# Touch_Pad_Board_PCB_A.net
KiCad netlist of a schematic drawn in EAGLE
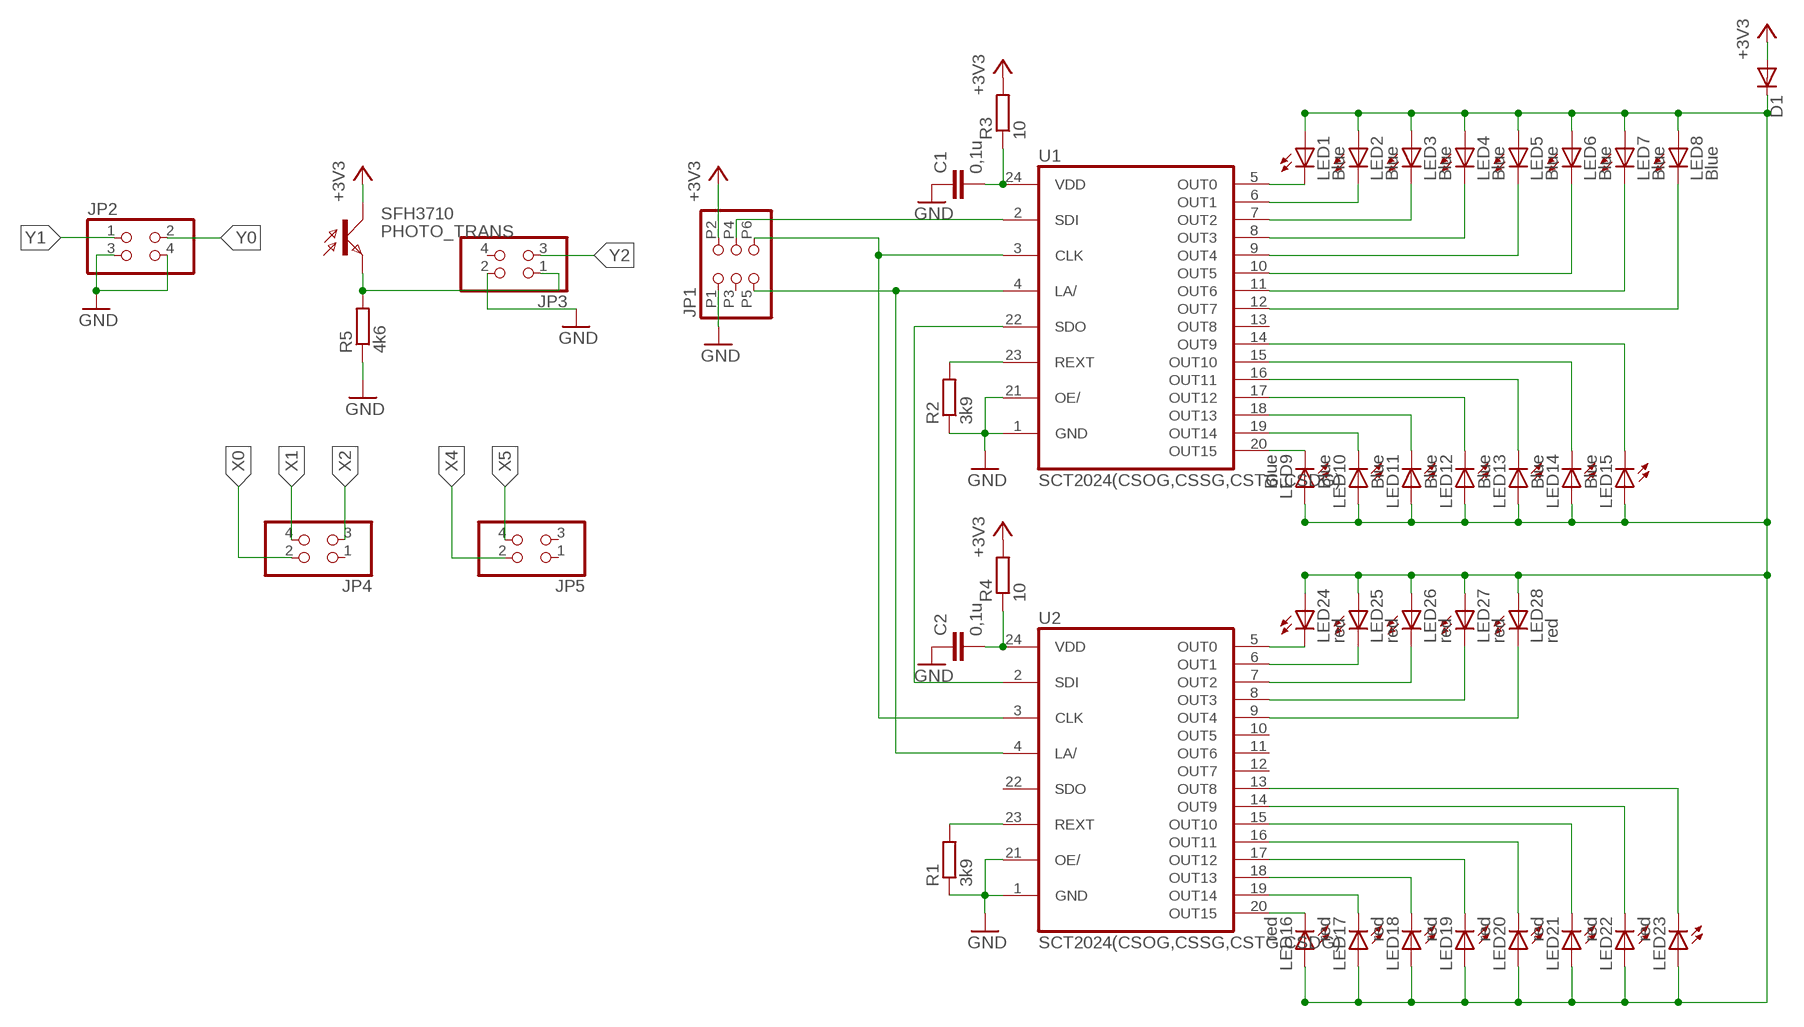
[diagram p0: schematic, sheet 1]

(export (version "E")
  (design (tool "Eeschema 10.0.6"))
  (components
    (comp (ref "C1")
      (value "0,1u")
      (footprint "eagle-import:C0805")
      (libsource (lib "eagle-import") (part "C-EUC0805"))
    )
    (comp (ref "C2")
      (value "0,1u")
      (footprint "eagle-import:C0805")
      (libsource (lib "eagle-import") (part "C-EUC0805"))
    )
    (comp (ref "D1")
      (value "DIODE-DO214AC")
      (footprint "eagle-import:DO214AC")
      (libsource (lib "eagle-import") (part "DIODE-DO214AC"))
    )
    (comp (ref "JP1")
      (value "PINHD-2X3SMD")
      (footprint "eagle-import:2X3SMD")
      (libsource (lib "eagle-import") (part "PINHD-2X3SMD"))
    )
    (comp (ref "JP2")
      (value "PINHD-2X2SMD")
      (footprint "eagle-import:2X2SMD")
      (libsource (lib "eagle-import") (part "PINHD-2X2SMD"))
    )
    (comp (ref "JP3")
      (value "PINHD-2X2SMD")
      (footprint "eagle-import:2X2SMD")
      (libsource (lib "eagle-import") (part "PINHD-2X2SMD"))
    )
    (comp (ref "JP4")
      (value "PINHD-2X2SMD")
      (footprint "eagle-import:2X2SMD")
      (libsource (lib "eagle-import") (part "PINHD-2X2SMD"))
    )
    (comp (ref "JP5")
      (value "PINHD-2X2SMD")
      (footprint "eagle-import:2X2SMD")
      (libsource (lib "eagle-import") (part "PINHD-2X2SMD"))
    )
    (comp (ref "LED1")
      (value "Blue")
      (footprint "eagle-import:CHIPLED_1206")
      (libsource (lib "eagle-import") (part "LEDCHIPLED_1206"))
    )
    (comp (ref "LED2")
      (value "Blue")
      (footprint "eagle-import:CHIPLED_1206")
      (libsource (lib "eagle-import") (part "LEDCHIPLED_1206"))
    )
    (comp (ref "LED3")
      (value "Blue")
      (footprint "eagle-import:CHIPLED_1206")
      (libsource (lib "eagle-import") (part "LEDCHIPLED_1206"))
    )
    (comp (ref "LED4")
      (value "Blue")
      (footprint "eagle-import:CHIPLED_1206")
      (libsource (lib "eagle-import") (part "LEDCHIPLED_1206"))
    )
    (comp (ref "LED5")
      (value "Blue")
      (footprint "eagle-import:CHIPLED_1206")
      (libsource (lib "eagle-import") (part "LEDCHIPLED_1206"))
    )
    (comp (ref "LED6")
      (value "Blue")
      (footprint "eagle-import:CHIPLED_1206")
      (libsource (lib "eagle-import") (part "LEDCHIPLED_1206"))
    )
    (comp (ref "LED7")
      (value "Blue")
      (footprint "eagle-import:CHIPLED_1206")
      (libsource (lib "eagle-import") (part "LEDCHIPLED_1206"))
    )
    (comp (ref "LED8")
      (value "Blue")
      (footprint "eagle-import:CHIPLED_1206")
      (libsource (lib "eagle-import") (part "LEDCHIPLED_1206"))
    )
    (comp (ref "LED9")
      (value "Blue")
      (footprint "eagle-import:CHIPLED_1206")
      (libsource (lib "eagle-import") (part "LEDCHIPLED_1206"))
    )
    (comp (ref "LED10")
      (value "Blue")
      (footprint "eagle-import:CHIPLED_1206")
      (libsource (lib "eagle-import") (part "LEDCHIPLED_1206"))
    )
    (comp (ref "LED11")
      (value "Blue")
      (footprint "eagle-import:CHIPLED_1206")
      (libsource (lib "eagle-import") (part "LEDCHIPLED_1206"))
    )
    (comp (ref "LED12")
      (value "Blue")
      (footprint "eagle-import:CHIPLED_1206")
      (libsource (lib "eagle-import") (part "LEDCHIPLED_1206"))
    )
    (comp (ref "LED13")
      (value "Blue")
      (footprint "eagle-import:CHIPLED_1206")
      (libsource (lib "eagle-import") (part "LEDCHIPLED_1206"))
    )
    (comp (ref "LED14")
      (value "Blue")
      (footprint "eagle-import:CHIPLED_1206")
      (libsource (lib "eagle-import") (part "LEDCHIPLED_1206"))
    )
    (comp (ref "LED15")
      (value "Blue")
      (footprint "eagle-import:CHIPLED_1206")
      (libsource (lib "eagle-import") (part "LEDCHIPLED_1206"))
    )
    (comp (ref "LED16")
      (value "red")
      (footprint "eagle-import:CHIPLED_1206")
      (libsource (lib "eagle-import") (part "LEDCHIPLED_1206"))
    )
    (comp (ref "LED17")
      (value "red")
      (footprint "eagle-import:CHIPLED_1206")
      (libsource (lib "eagle-import") (part "LEDCHIPLED_1206"))
    )
    (comp (ref "LED18")
      (value "red")
      (footprint "eagle-import:CHIPLED_1206")
      (libsource (lib "eagle-import") (part "LEDCHIPLED_1206"))
    )
    (comp (ref "LED19")
      (value "red")
      (footprint "eagle-import:CHIPLED_1206")
      (libsource (lib "eagle-import") (part "LEDCHIPLED_1206"))
    )
    (comp (ref "LED20")
      (value "red")
      (footprint "eagle-import:CHIPLED_1206")
      (libsource (lib "eagle-import") (part "LEDCHIPLED_1206"))
    )
    (comp (ref "LED21")
      (value "red")
      (footprint "eagle-import:CHIPLED_1206")
      (libsource (lib "eagle-import") (part "LEDCHIPLED_1206"))
    )
    (comp (ref "LED22")
      (value "red")
      (footprint "eagle-import:CHIPLED_1206")
      (libsource (lib "eagle-import") (part "LEDCHIPLED_1206"))
    )
    (comp (ref "LED23")
      (value "red")
      (footprint "eagle-import:CHIPLED_1206")
      (libsource (lib "eagle-import") (part "LEDCHIPLED_1206"))
    )
    (comp (ref "LED24")
      (value "red")
      (footprint "eagle-import:CHIPLED_1206")
      (libsource (lib "eagle-import") (part "LEDCHIPLED_1206"))
    )
    (comp (ref "LED25")
      (value "red")
      (footprint "eagle-import:CHIPLED_1206")
      (libsource (lib "eagle-import") (part "LEDCHIPLED_1206"))
    )
    (comp (ref "LED26")
      (value "red")
      (footprint "eagle-import:CHIPLED_1206")
      (libsource (lib "eagle-import") (part "LEDCHIPLED_1206"))
    )
    (comp (ref "LED27")
      (value "red")
      (footprint "eagle-import:CHIPLED_1206")
      (libsource (lib "eagle-import") (part "LEDCHIPLED_1206"))
    )
    (comp (ref "LED28")
      (value "red")
      (footprint "eagle-import:CHIPLED_1206")
      (libsource (lib "eagle-import") (part "LEDCHIPLED_1206"))
    )
    (comp (ref "R1")
      (value "3k9")
      (footprint "eagle-import:R0805")
      (libsource (lib "eagle-import") (part "R-EU_R0805"))
    )
    (comp (ref "R2")
      (value "3k9")
      (footprint "eagle-import:R0805")
      (libsource (lib "eagle-import") (part "R-EU_R0805"))
    )
    (comp (ref "R3")
      (value "10")
      (footprint "eagle-import:R0805")
      (libsource (lib "eagle-import") (part "R-EU_R0805"))
    )
    (comp (ref "R4")
      (value "10")
      (footprint "eagle-import:R0805")
      (libsource (lib "eagle-import") (part "R-EU_R0805"))
    )
    (comp (ref "R5")
      (value "4k6")
      (footprint "eagle-import:R0805")
      (libsource (lib "eagle-import") (part "R-EU_R0805"))
    )
    (comp (ref "SFH3710")
      (value "PHOTO_TRANS")
      (footprint "eagle-import:PHOTO_TRANS")
      (libsource (lib "eagle-import") (part "PHOTO_TRANS"))
    )
    (comp (ref "U1")
      (value "SCT2024(CSOG,CSSG,CSTG,CSDG)")
      (footprint "eagle-import:24SSOP")
      (libsource (lib "eagle-import") (part "SCT2024(CSOG,CSSG,CSTG,CSDG)"))
    )
    (comp (ref "U2")
      (value "SCT2024(CSOG,CSSG,CSTG,CSDG)")
      (footprint "eagle-import:24SSOP")
      (libsource (lib "eagle-import") (part "SCT2024(CSOG,CSSG,CSTG,CSDG)"))
    )
  )
  (nets
    (net (code "1") (name "+3V3") (class "Default")
      (node (ref "D1") (pin "A") (pinfunction "A_A") (pintype "passive"))
      (node (ref "JP1") (pin "P2") (pinfunction "2_P2") (pintype "passive"))
      (node (ref "R3") (pin "2") (pinfunction "2_2") (pintype "passive"))
      (node (ref "R4") (pin "2") (pinfunction "2_2") (pintype "passive"))
      (node (ref "SFH3710") (pin "A") (pinfunction "C_A") (pintype "passive"))
    )
    (net (code "2") (name "GND") (class "Default")
      (node (ref "C1") (pin "1") (pinfunction "1_1") (pintype "passive"))
      (node (ref "C2") (pin "1") (pinfunction "1_1") (pintype "passive"))
      (node (ref "JP1") (pin "P1") (pinfunction "1_P1") (pintype "passive"))
      (node (ref "JP2") (pin "3") (pinfunction "3_3") (pintype "passive"))
      (node (ref "JP2") (pin "4") (pinfunction "4_4") (pintype "passive"))
      (node (ref "JP3") (pin "2") (pinfunction "2_2") (pintype "passive"))
      (node (ref "R1") (pin "1") (pinfunction "1_1") (pintype "passive"))
      (node (ref "R2") (pin "1") (pinfunction "1_1") (pintype "passive"))
      (node (ref "R5") (pin "1") (pinfunction "1_1") (pintype "passive"))
      (node (ref "U1") (pin "1") (pinfunction "GND_1") (pintype "power_in"))
      (node (ref "U1") (pin "21") (pinfunction "OE/_21") (pintype "bidirectional"))
      (node (ref "U2") (pin "1") (pinfunction "GND_1") (pintype "power_in"))
      (node (ref "U2") (pin "21") (pinfunction "OE/_21") (pintype "bidirectional"))
    )
    (net (code "3") (name "Net-(D1-PadC)") (class "Default")
      (node (ref "D1") (pin "C") (pinfunction "C_C") (pintype "passive"))
      (node (ref "LED1") (pin "A") (pinfunction "A_A") (pintype "passive"))
      (node (ref "LED10") (pin "A") (pinfunction "A_A") (pintype "passive"))
      (node (ref "LED11") (pin "A") (pinfunction "A_A") (pintype "passive"))
      (node (ref "LED12") (pin "A") (pinfunction "A_A") (pintype "passive"))
      (node (ref "LED13") (pin "A") (pinfunction "A_A") (pintype "passive"))
      (node (ref "LED14") (pin "A") (pinfunction "A_A") (pintype "passive"))
      (node (ref "LED15") (pin "A") (pinfunction "A_A") (pintype "passive"))
      (node (ref "LED16") (pin "A") (pinfunction "A_A") (pintype "passive"))
      (node (ref "LED17") (pin "A") (pinfunction "A_A") (pintype "passive"))
      (node (ref "LED18") (pin "A") (pinfunction "A_A") (pintype "passive"))
      (node (ref "LED19") (pin "A") (pinfunction "A_A") (pintype "passive"))
      (node (ref "LED2") (pin "A") (pinfunction "A_A") (pintype "passive"))
      (node (ref "LED20") (pin "A") (pinfunction "A_A") (pintype "passive"))
      (node (ref "LED21") (pin "A") (pinfunction "A_A") (pintype "passive"))
      (node (ref "LED22") (pin "A") (pinfunction "A_A") (pintype "passive"))
      (node (ref "LED23") (pin "A") (pinfunction "A_A") (pintype "passive"))
      (node (ref "LED24") (pin "A") (pinfunction "A_A") (pintype "passive"))
      (node (ref "LED25") (pin "A") (pinfunction "A_A") (pintype "passive"))
      (node (ref "LED26") (pin "A") (pinfunction "A_A") (pintype "passive"))
      (node (ref "LED27") (pin "A") (pinfunction "A_A") (pintype "passive"))
      (node (ref "LED28") (pin "A") (pinfunction "A_A") (pintype "passive"))
      (node (ref "LED3") (pin "A") (pinfunction "A_A") (pintype "passive"))
      (node (ref "LED4") (pin "A") (pinfunction "A_A") (pintype "passive"))
      (node (ref "LED5") (pin "A") (pinfunction "A_A") (pintype "passive"))
      (node (ref "LED6") (pin "A") (pinfunction "A_A") (pintype "passive"))
      (node (ref "LED7") (pin "A") (pinfunction "A_A") (pintype "passive"))
      (node (ref "LED8") (pin "A") (pinfunction "A_A") (pintype "passive"))
      (node (ref "LED9") (pin "A") (pinfunction "A_A") (pintype "passive"))
    )
    (net (code "4") (name "Net-(JP1-4)") (class "Default")
      (node (ref "JP1") (pin "P4") (pinfunction "4_P4") (pintype "passive"))
      (node (ref "U1") (pin "2") (pinfunction "SDI_2") (pintype "input"))
    )
    (net (code "5") (name "Net-(JP1-5)") (class "Default")
      (node (ref "JP1") (pin "P5") (pinfunction "5_P5") (pintype "passive"))
      (node (ref "U1") (pin "4") (pinfunction "LA/_4") (pintype "bidirectional"))
      (node (ref "U2") (pin "4") (pinfunction "LA/_4") (pintype "bidirectional"))
    )
    (net (code "6") (name "Net-(JP1-6)") (class "Default")
      (node (ref "JP1") (pin "P6") (pinfunction "6_P6") (pintype "passive"))
      (node (ref "U1") (pin "3") (pinfunction "CLK_3") (pintype "input"))
      (node (ref "U2") (pin "3") (pinfunction "CLK_3") (pintype "input"))
    )
    (net (code "7") (name "Net-(SFH3710-E)") (class "Default")
      (node (ref "JP3") (pin "1") (pinfunction "1_1") (pintype "passive"))
      (node (ref "R5") (pin "2") (pinfunction "2_2") (pintype "passive"))
      (node (ref "SFH3710") (pin "C") (pinfunction "E_C") (pintype "passive"))
    )
    (net (code "8") (name "Net-(U1-OUT0)") (class "Default")
      (node (ref "LED1") (pin "C") (pinfunction "C_C") (pintype "passive"))
      (node (ref "U1") (pin "5") (pinfunction "OUT0_5") (pintype "output"))
    )
    (net (code "9") (name "Net-(U1-OUT1)") (class "Default")
      (node (ref "LED2") (pin "C") (pinfunction "C_C") (pintype "passive"))
      (node (ref "U1") (pin "6") (pinfunction "OUT1_6") (pintype "output"))
    )
    (net (code "10") (name "Net-(U1-OUT2)") (class "Default")
      (node (ref "LED3") (pin "C") (pinfunction "C_C") (pintype "passive"))
      (node (ref "U1") (pin "7") (pinfunction "OUT2_7") (pintype "output"))
    )
    (net (code "11") (name "Net-(U1-OUT3)") (class "Default")
      (node (ref "LED4") (pin "C") (pinfunction "C_C") (pintype "passive"))
      (node (ref "U1") (pin "8") (pinfunction "OUT3_8") (pintype "output"))
    )
    (net (code "12") (name "Net-(U1-OUT4)") (class "Default")
      (node (ref "LED5") (pin "C") (pinfunction "C_C") (pintype "passive"))
      (node (ref "U1") (pin "9") (pinfunction "OUT4_9") (pintype "output"))
    )
    (net (code "13") (name "Net-(U1-OUT5)") (class "Default")
      (node (ref "LED6") (pin "C") (pinfunction "C_C") (pintype "passive"))
      (node (ref "U1") (pin "10") (pinfunction "OUT5_10") (pintype "output"))
    )
    (net (code "14") (name "Net-(U1-OUT6)") (class "Default")
      (node (ref "LED7") (pin "C") (pinfunction "C_C") (pintype "passive"))
      (node (ref "U1") (pin "11") (pinfunction "OUT6_11") (pintype "output"))
    )
    (net (code "15") (name "Net-(U1-OUT7)") (class "Default")
      (node (ref "LED8") (pin "C") (pinfunction "C_C") (pintype "passive"))
      (node (ref "U1") (pin "12") (pinfunction "OUT7_12") (pintype "output"))
    )
    (net (code "16") (name "Net-(U1-OUT9)") (class "Default")
      (node (ref "LED15") (pin "C") (pinfunction "C_C") (pintype "passive"))
      (node (ref "U1") (pin "14") (pinfunction "OUT9_14") (pintype "output"))
    )
    (net (code "17") (name "Net-(U1-OUT10)") (class "Default")
      (node (ref "LED14") (pin "C") (pinfunction "C_C") (pintype "passive"))
      (node (ref "U1") (pin "15") (pinfunction "OUT10_15") (pintype "output"))
    )
    (net (code "18") (name "Net-(U1-OUT11)") (class "Default")
      (node (ref "LED13") (pin "C") (pinfunction "C_C") (pintype "passive"))
      (node (ref "U1") (pin "16") (pinfunction "OUT11_16") (pintype "output"))
    )
    (net (code "19") (name "Net-(U1-OUT12)") (class "Default")
      (node (ref "LED12") (pin "C") (pinfunction "C_C") (pintype "passive"))
      (node (ref "U1") (pin "17") (pinfunction "OUT12_17") (pintype "output"))
    )
    (net (code "20") (name "Net-(U1-OUT13)") (class "Default")
      (node (ref "LED11") (pin "C") (pinfunction "C_C") (pintype "passive"))
      (node (ref "U1") (pin "18") (pinfunction "OUT13_18") (pintype "output"))
    )
    (net (code "21") (name "Net-(U1-OUT14)") (class "Default")
      (node (ref "LED10") (pin "C") (pinfunction "C_C") (pintype "passive"))
      (node (ref "U1") (pin "19") (pinfunction "OUT14_19") (pintype "output"))
    )
    (net (code "22") (name "Net-(U1-OUT15)") (class "Default")
      (node (ref "LED9") (pin "C") (pinfunction "C_C") (pintype "passive"))
      (node (ref "U1") (pin "20") (pinfunction "OUT15_20") (pintype "output"))
    )
    (net (code "23") (name "Net-(U1-REXT)") (class "Default")
      (node (ref "R2") (pin "2") (pinfunction "2_2") (pintype "passive"))
      (node (ref "U1") (pin "23") (pinfunction "REXT_23") (pintype "power_in"))
    )
    (net (code "24") (name "Net-(U1-SDO)") (class "Default")
      (node (ref "U1") (pin "22") (pinfunction "SDO_22") (pintype "output"))
      (node (ref "U2") (pin "2") (pinfunction "SDI_2") (pintype "input"))
    )
    (net (code "25") (name "Net-(U1-VDD)") (class "Default")
      (node (ref "C1") (pin "2") (pinfunction "2_2") (pintype "passive"))
      (node (ref "R3") (pin "1") (pinfunction "1_1") (pintype "passive"))
      (node (ref "U1") (pin "24") (pinfunction "VDD_24") (pintype "bidirectional"))
    )
    (net (code "26") (name "Net-(U2-OUT0)") (class "Default")
      (node (ref "LED24") (pin "C") (pinfunction "C_C") (pintype "passive"))
      (node (ref "U2") (pin "5") (pinfunction "OUT0_5") (pintype "output"))
    )
    (net (code "27") (name "Net-(U2-OUT1)") (class "Default")
      (node (ref "LED25") (pin "C") (pinfunction "C_C") (pintype "passive"))
      (node (ref "U2") (pin "6") (pinfunction "OUT1_6") (pintype "output"))
    )
    (net (code "28") (name "Net-(U2-OUT2)") (class "Default")
      (node (ref "LED26") (pin "C") (pinfunction "C_C") (pintype "passive"))
      (node (ref "U2") (pin "7") (pinfunction "OUT2_7") (pintype "output"))
    )
    (net (code "29") (name "Net-(U2-OUT3)") (class "Default")
      (node (ref "LED27") (pin "C") (pinfunction "C_C") (pintype "passive"))
      (node (ref "U2") (pin "8") (pinfunction "OUT3_8") (pintype "output"))
    )
    (net (code "30") (name "Net-(U2-OUT4)") (class "Default")
      (node (ref "LED28") (pin "C") (pinfunction "C_C") (pintype "passive"))
      (node (ref "U2") (pin "9") (pinfunction "OUT4_9") (pintype "output"))
    )
    (net (code "31") (name "Net-(U2-OUT8)") (class "Default")
      (node (ref "LED23") (pin "C") (pinfunction "C_C") (pintype "passive"))
      (node (ref "U2") (pin "13") (pinfunction "OUT8_13") (pintype "output"))
    )
    (net (code "32") (name "Net-(U2-OUT9)") (class "Default")
      (node (ref "LED22") (pin "C") (pinfunction "C_C") (pintype "passive"))
      (node (ref "U2") (pin "14") (pinfunction "OUT9_14") (pintype "output"))
    )
    (net (code "33") (name "Net-(U2-OUT10)") (class "Default")
      (node (ref "LED21") (pin "C") (pinfunction "C_C") (pintype "passive"))
      (node (ref "U2") (pin "15") (pinfunction "OUT10_15") (pintype "output"))
    )
    (net (code "34") (name "Net-(U2-OUT11)") (class "Default")
      (node (ref "LED20") (pin "C") (pinfunction "C_C") (pintype "passive"))
      (node (ref "U2") (pin "16") (pinfunction "OUT11_16") (pintype "output"))
    )
    (net (code "35") (name "Net-(U2-OUT12)") (class "Default")
      (node (ref "LED19") (pin "C") (pinfunction "C_C") (pintype "passive"))
      (node (ref "U2") (pin "17") (pinfunction "OUT12_17") (pintype "output"))
    )
    (net (code "36") (name "Net-(U2-OUT13)") (class "Default")
      (node (ref "LED18") (pin "C") (pinfunction "C_C") (pintype "passive"))
      (node (ref "U2") (pin "18") (pinfunction "OUT13_18") (pintype "output"))
    )
    (net (code "37") (name "Net-(U2-OUT14)") (class "Default")
      (node (ref "LED17") (pin "C") (pinfunction "C_C") (pintype "passive"))
      (node (ref "U2") (pin "19") (pinfunction "OUT14_19") (pintype "output"))
    )
    (net (code "38") (name "Net-(U2-OUT15)") (class "Default")
      (node (ref "LED16") (pin "C") (pinfunction "C_C") (pintype "passive"))
      (node (ref "U2") (pin "20") (pinfunction "OUT15_20") (pintype "output"))
    )
    (net (code "39") (name "Net-(U2-REXT)") (class "Default")
      (node (ref "R1") (pin "2") (pinfunction "2_2") (pintype "passive"))
      (node (ref "U2") (pin "23") (pinfunction "REXT_23") (pintype "power_in"))
    )
    (net (code "40") (name "Net-(U2-VDD)") (class "Default")
      (node (ref "C2") (pin "2") (pinfunction "2_2") (pintype "passive"))
      (node (ref "R4") (pin "1") (pinfunction "1_1") (pintype "passive"))
      (node (ref "U2") (pin "24") (pinfunction "VDD_24") (pintype "bidirectional"))
    )
    (net (code "41") (name "X0") (class "Default")
      (node (ref "JP4") (pin "2") (pinfunction "2_2") (pintype "passive"))
    )
    (net (code "42") (name "X1") (class "Default")
      (node (ref "JP4") (pin "4") (pinfunction "4_4") (pintype "passive"))
    )
    (net (code "43") (name "X2") (class "Default")
      (node (ref "JP4") (pin "3") (pinfunction "3_3") (pintype "passive"))
    )
    (net (code "44") (name "X4") (class "Default")
      (node (ref "JP5") (pin "2") (pinfunction "2_2") (pintype "passive"))
    )
    (net (code "45") (name "X5") (class "Default")
      (node (ref "JP5") (pin "4") (pinfunction "4_4") (pintype "passive"))
    )
    (net (code "46") (name "Y0") (class "Default")
      (node (ref "JP2") (pin "2") (pinfunction "2_2") (pintype "passive"))
    )
    (net (code "47") (name "Y1") (class "Default")
      (node (ref "JP2") (pin "1") (pinfunction "1_1") (pintype "passive"))
    )
    (net (code "48") (name "Y2") (class "Default")
      (node (ref "JP3") (pin "3") (pinfunction "3_3") (pintype "passive"))
    )
    (net (code "49") (name "unconnected-(JP1-3-PadP3)") (class "Default")
      (node (ref "JP1") (pin "P3") (pinfunction "3_P3") (pintype "passive"))
    )
    (net (code "50") (name "unconnected-(JP3-Pad4)") (class "Default")
      (node (ref "JP3") (pin "4") (pinfunction "4_4") (pintype "passive"))
    )
    (net (code "51") (name "unconnected-(JP4-Pad1)") (class "Default")
      (node (ref "JP4") (pin "1") (pinfunction "1_1") (pintype "passive"))
    )
    (net (code "52") (name "unconnected-(JP5-Pad1)") (class "Default")
      (node (ref "JP5") (pin "1") (pinfunction "1_1") (pintype "passive"))
    )
    (net (code "53") (name "unconnected-(JP5-Pad3)") (class "Default")
      (node (ref "JP5") (pin "3") (pinfunction "3_3") (pintype "passive"))
    )
    (net (code "54") (name "unconnected-(U1-OUT8-Pad13)") (class "Default")
      (node (ref "U1") (pin "13") (pinfunction "OUT8_13") (pintype "output"))
    )
    (net (code "55") (name "unconnected-(U2-OUT5-Pad10)") (class "Default")
      (node (ref "U2") (pin "10") (pinfunction "OUT5_10") (pintype "output"))
    )
    (net (code "56") (name "unconnected-(U2-OUT6-Pad11)") (class "Default")
      (node (ref "U2") (pin "11") (pinfunction "OUT6_11") (pintype "output"))
    )
    (net (code "57") (name "unconnected-(U2-OUT7-Pad12)") (class "Default")
      (node (ref "U2") (pin "12") (pinfunction "OUT7_12") (pintype "output"))
    )
    (net (code "58") (name "unconnected-(U2-SDO-Pad22)") (class "Default")
      (node (ref "U2") (pin "22") (pinfunction "SDO_22") (pintype "output"))
    )
  )
)
